# STELLA.net
KiCad netlist of a schematic drawn in EAGLE
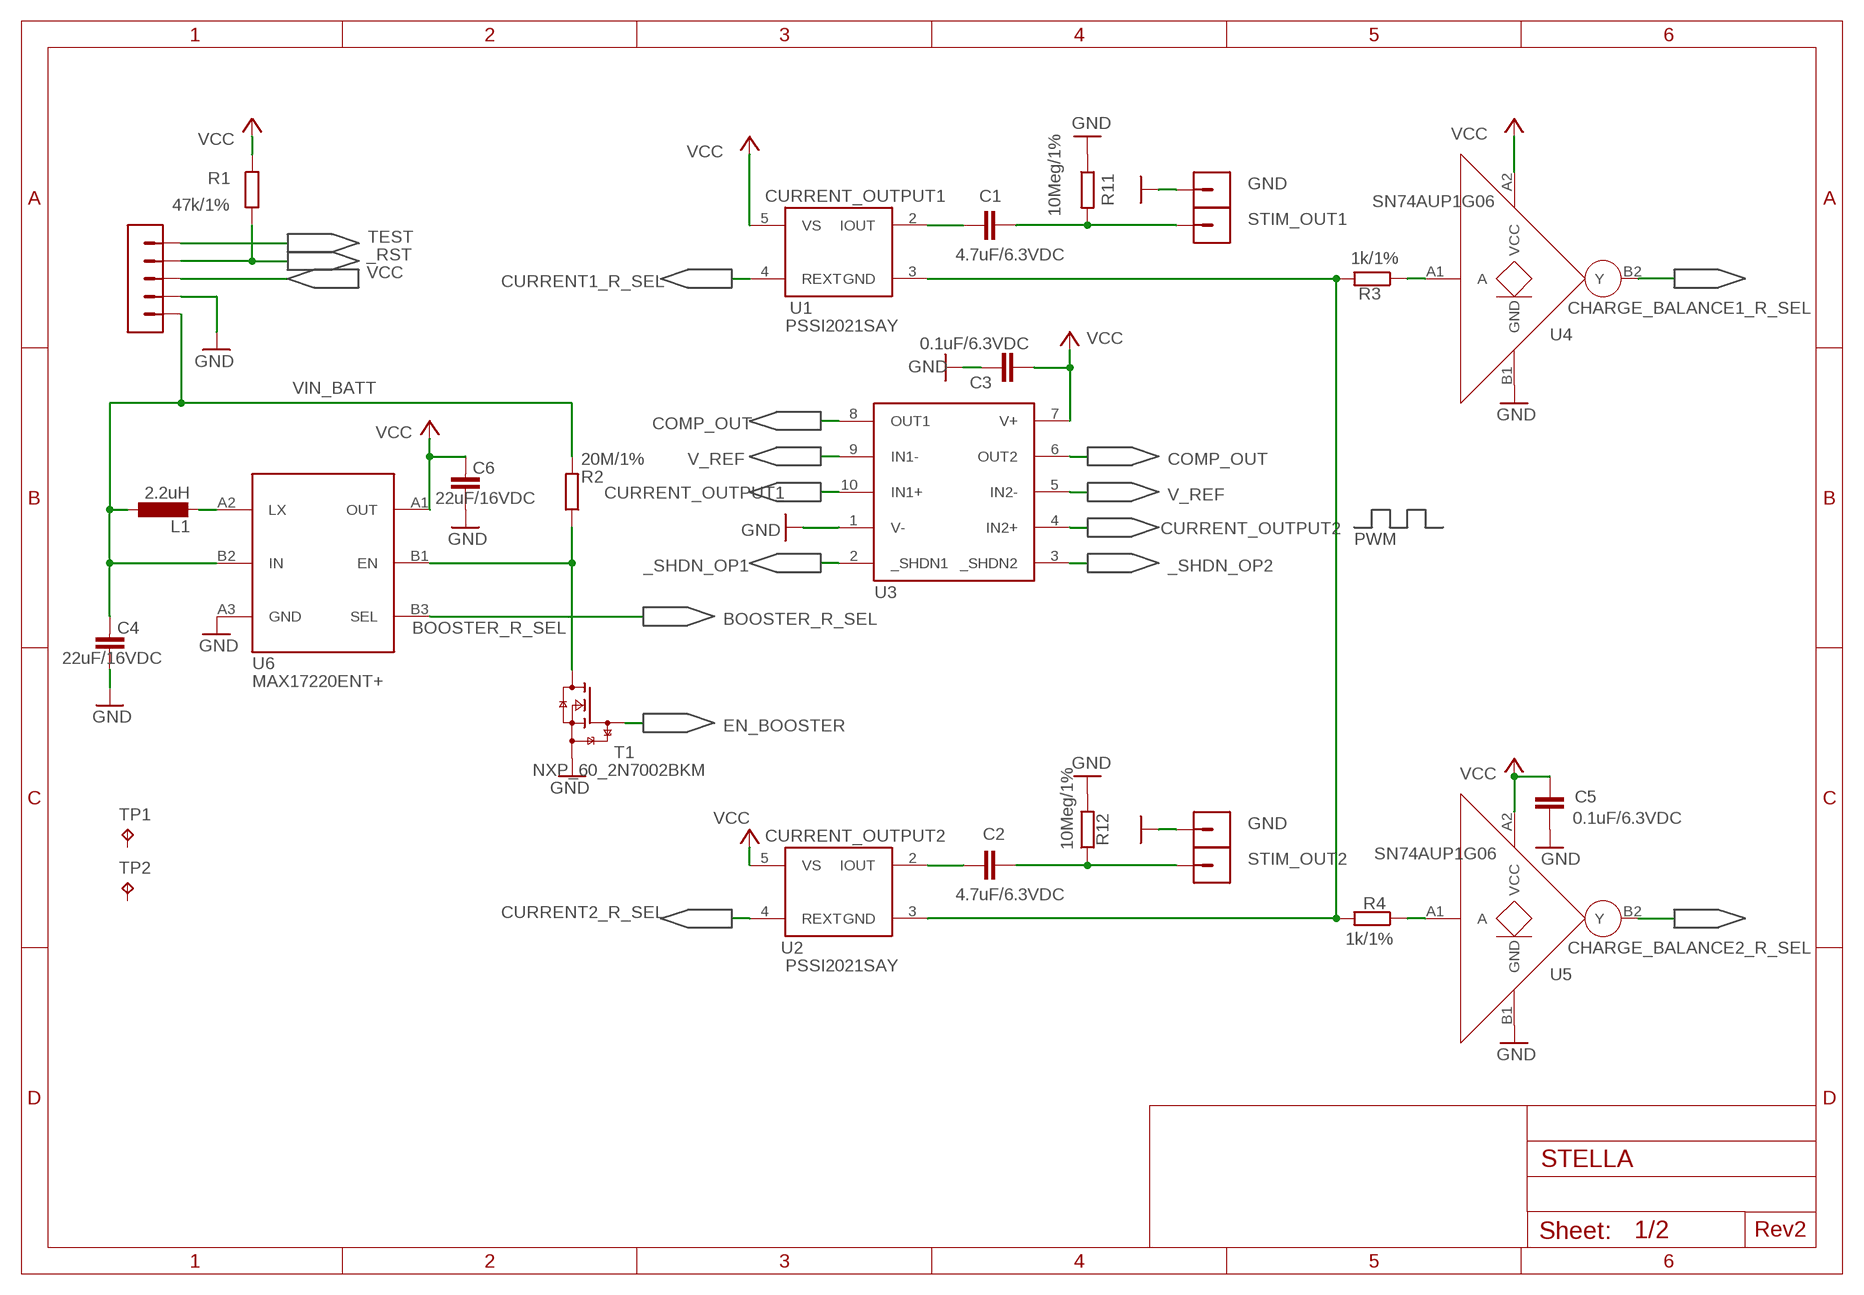
[diagram p0: schematic, sheet 1]
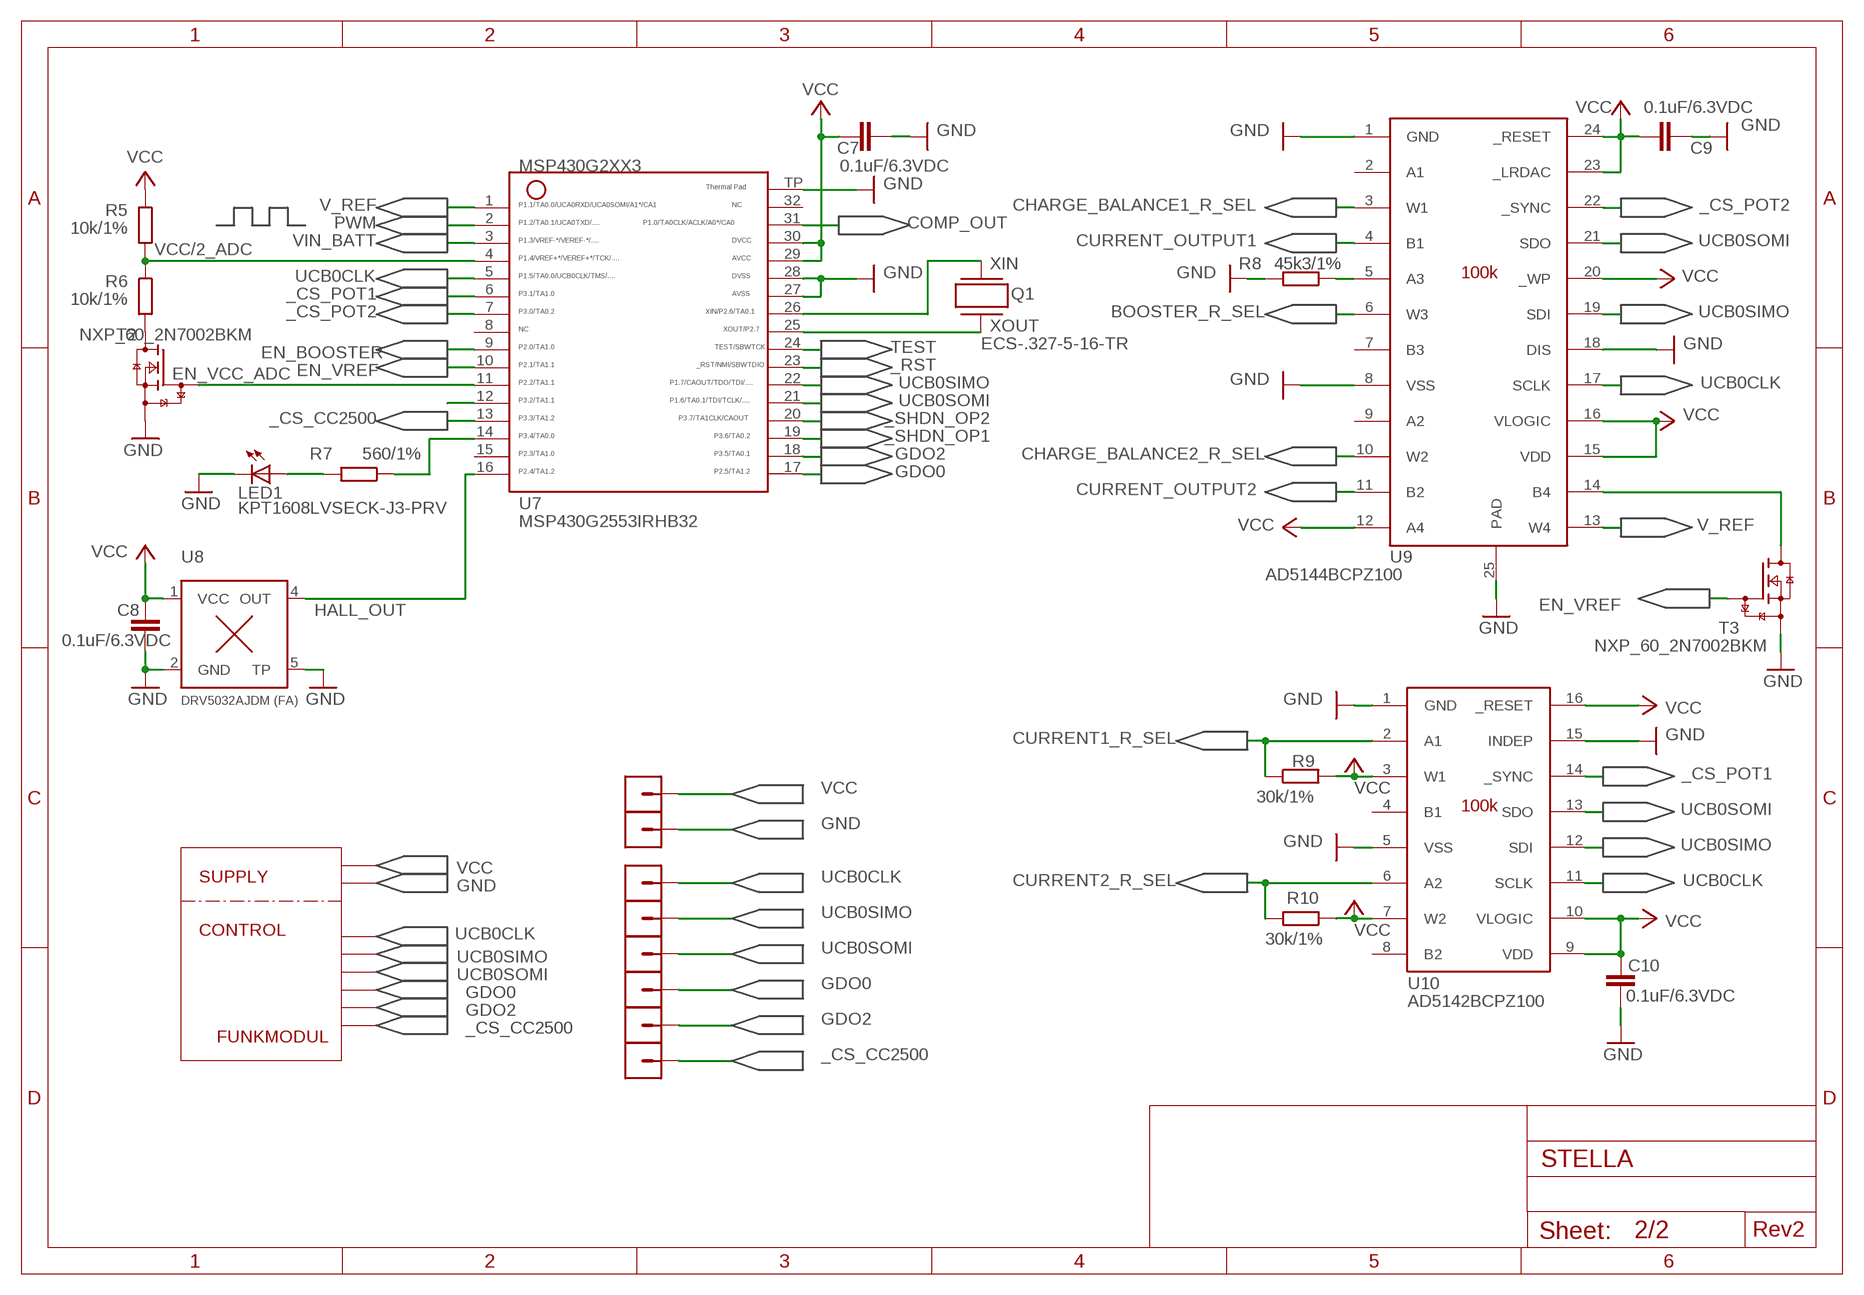
[diagram p1: schematic, sheet 2]

(export (version "E")
  (design (tool "Eeschema 10.0.6"))
  (components
    (comp (ref "C7")
      (value "0.1uF/6.3VDC")
      (footprint "eagle-import:C0402")
      (libsource (lib "eagle-import") (part "C-EUC0402"))
    )
    (comp (ref "C8")
      (value "0.1uF/6.3VDC")
      (footprint "eagle-import:C0402")
      (libsource (lib "eagle-import") (part "C-EUC0402"))
    )
    (comp (ref "C9")
      (value "0.1uF/6.3VDC")
      (footprint "eagle-import:C0402")
      (libsource (lib "eagle-import") (part "C-EUC0402"))
    )
    (comp (ref "C10")
      (value "0.1uF/6.3VDC")
      (footprint "eagle-import:C0402")
      (libsource (lib "eagle-import") (part "C-EUC0402"))
    )
    (comp (ref "LED1")
      (value "KPT1608LVSECK-J3-PRV")
      (footprint "eagle-import:LED_CHIP-LED0603")
      (libsource (lib "eagle-import") (part "LED_LEDCHIP-LED0603"))
    )
    (comp (ref "Q1")
      (value "ECS-.327-5-16-TR")
      (footprint "eagle-import:CRYSTAL_ECX_16_32768_ECX-16")
      (libsource (lib "eagle-import") (part "CRYSTAL_ECX_16_32768_ECX-16"))
    )
    (comp (ref "R5")
      (value "10k/1%")
      (footprint "eagle-import:R0402")
      (libsource (lib "eagle-import") (part "R-EU_R0402"))
    )
    (comp (ref "R6")
      (value "10k/1%")
      (footprint "eagle-import:R0402")
      (libsource (lib "eagle-import") (part "R-EU_R0402"))
    )
    (comp (ref "R7")
      (value "560/1%")
      (footprint "eagle-import:R0402")
      (libsource (lib "eagle-import") (part "R-EU_R0402"))
    )
    (comp (ref "R8")
      (value "45k3/1%")
      (footprint "eagle-import:R0402")
      (libsource (lib "eagle-import") (part "R-EU_R0402"))
    )
    (comp (ref "R9")
      (value "30k/1%")
      (footprint "eagle-import:R0402")
      (libsource (lib "eagle-import") (part "R-EU_R0402"))
    )
    (comp (ref "R10")
      (value "30k/1%")
      (footprint "eagle-import:R0402")
      (libsource (lib "eagle-import") (part "R-EU_R0402"))
    )
    (comp (ref "T2")
      (value "NXP_60_2N7002BKM")
      (footprint "eagle-import:NXP_60_SOT883(B)")
      (libsource (lib "eagle-import") (part "NXP_60_2N7002BKM"))
    )
    (comp (ref "T3")
      (value "NXP_60_2N7002BKM")
      (footprint "eagle-import:NXP_60_SOT883(B)")
      (libsource (lib "eagle-import") (part "NXP_60_2N7002BKM"))
    )
    (comp (ref "U7")
      (value "MSP430G2553IRHB32")
      (footprint "eagle-import:RHB32")
      (libsource (lib "eagle-import") (part "G2XX3---RHB32"))
    )
    (comp (ref "U8")
      (value "DRV5032AJDM (FA)")
      (footprint "eagle-import:DRV5032_DRV5032_X2SON")
      (libsource (lib "eagle-import") (part "DRV5032_DRV5032"))
    )
    (comp (ref "U9")
      (value "AD5144BCPZ100")
      (footprint "eagle-import:AD5144_AD5144_LFCSP")
      (libsource (lib "eagle-import") (part "AD5144_AD5144"))
    )
    (comp (ref "U10")
      (value "AD5142BCPZ100")
      (footprint "eagle-import:AD5122_AD5142_LFCSP")
      (libsource (lib "eagle-import") (part "AD5122_AD5142"))
    )
    (comp (ref "X6")
      (value "1PIN_INTERFACE")
      (footprint "eagle-import:1PIN_INTERFACE")
      (libsource (lib "eagle-import") (part "1PIN_INTERFACE"))
    )
    (comp (ref "X7")
      (value "1PIN_INTERFACE")
      (footprint "eagle-import:1PIN_INTERFACE")
      (libsource (lib "eagle-import") (part "1PIN_INTERFACE"))
    )
    (comp (ref "X8")
      (value "1PIN_INTERFACE")
      (footprint "eagle-import:1PIN_INTERFACE")
      (libsource (lib "eagle-import") (part "1PIN_INTERFACE"))
    )
    (comp (ref "X9")
      (value "1PIN_INTERFACE")
      (footprint "eagle-import:1PIN_INTERFACE")
      (libsource (lib "eagle-import") (part "1PIN_INTERFACE"))
    )
    (comp (ref "X10")
      (value "1PIN_INTERFACE")
      (footprint "eagle-import:1PIN_INTERFACE")
      (libsource (lib "eagle-import") (part "1PIN_INTERFACE"))
    )
    (comp (ref "X11")
      (value "1PIN_INTERFACE")
      (footprint "eagle-import:1PIN_INTERFACE")
      (libsource (lib "eagle-import") (part "1PIN_INTERFACE"))
    )
    (comp (ref "X12")
      (value "1PIN_INTERFACE")
      (footprint "eagle-import:1PIN_INTERFACE")
      (libsource (lib "eagle-import") (part "1PIN_INTERFACE"))
    )
    (comp (ref "X13")
      (value "1PIN_INTERFACE")
      (footprint "eagle-import:1PIN_INTERFACE")
      (libsource (lib "eagle-import") (part "1PIN_INTERFACE"))
    )
    (comp (ref "C1")
      (value "4.7uF/6.3VDC")
      (footprint "eagle-import:C0402")
      (libsource (lib "eagle-import") (part "C-EUC0402"))
    )
    (comp (ref "C2")
      (value "4.7uF/6.3VDC")
      (footprint "eagle-import:C0402")
      (libsource (lib "eagle-import") (part "C-EUC0402"))
    )
    (comp (ref "C3")
      (value "0.1uF/6.3VDC")
      (footprint "eagle-import:C0402")
      (libsource (lib "eagle-import") (part "C-EUC0402"))
    )
    (comp (ref "C4")
      (value "22uF/16VDC")
      (footprint "eagle-import:MYRCL_0603")
      (libsource (lib "eagle-import") (part "MYRCL_C0603"))
    )
    (comp (ref "C5")
      (value "0.1uF/6.3VDC")
      (footprint "eagle-import:C0402")
      (libsource (lib "eagle-import") (part "C-EUC0402"))
    )
    (comp (ref "C6")
      (value "22uF/16VDC")
      (footprint "eagle-import:MYRCL_0603")
      (libsource (lib "eagle-import") (part "MYRCL_C0603"))
    )
    (comp (ref "L1")
      (value "2.2uH")
      (footprint "eagle-import:L0402")
      (libsource (lib "eagle-import") (part "L-EU"))
    )
    (comp (ref "R1")
      (value "47k/1%")
      (footprint "eagle-import:R0402")
      (libsource (lib "eagle-import") (part "R-EU_R0402"))
    )
    (comp (ref "R2")
      (value "20M/1%")
      (footprint "eagle-import:R0402")
      (libsource (lib "eagle-import") (part "R-EU_R0402"))
    )
    (comp (ref "R3")
      (value "1k/1%")
      (footprint "eagle-import:R0402")
      (libsource (lib "eagle-import") (part "R-EU_R0402"))
    )
    (comp (ref "R4")
      (value "1k/1%")
      (footprint "eagle-import:R0402")
      (libsource (lib "eagle-import") (part "R-EU_R0402"))
    )
    (comp (ref "R11")
      (value "10Meg/1%")
      (footprint "eagle-import:R0402")
      (libsource (lib "eagle-import") (part "R-EU_R0402"))
    )
    (comp (ref "R12")
      (value "10Meg/1%")
      (footprint "eagle-import:R0402")
      (libsource (lib "eagle-import") (part "R-EU_R0402"))
    )
    (comp (ref "T1")
      (value "NXP_60_2N7002BKM")
      (footprint "eagle-import:NXP_60_SOT883(B)")
      (libsource (lib "eagle-import") (part "NXP_60_2N7002BKM"))
    )
    (comp (ref "TP1")
      (value "TPTP06SQ")
      (footprint "eagle-import:TP06SQ")
      (libsource (lib "eagle-import") (part "TPTP06SQ"))
    )
    (comp (ref "TP2")
      (value "TPTP06SQ")
      (footprint "eagle-import:TP06SQ")
      (libsource (lib "eagle-import") (part "TPTP06SQ"))
    )
    (comp (ref "U1")
      (value "PSSI2021SAY")
      (footprint "eagle-import:SOT353")
      (libsource (lib "eagle-import") (part "PSSI2021SAY"))
    )
    (comp (ref "U2")
      (value "PSSI2021SAY")
      (footprint "eagle-import:SOT353")
      (libsource (lib "eagle-import") (part "PSSI2021SAY"))
    )
    (comp (ref "U3")
      (value "TLV_9002S_TLV9002S_RUG")
      (footprint "eagle-import:TLV_9002S_TLV9002S_RUG")
      (libsource (lib "eagle-import") (part "TLV_9002S_TLV9002S_RUG"))
    )
    (comp (ref "U4")
      (value "SN74AUP1G06")
      (footprint "eagle-import:SN74AUP1G06_SN74AUP1G06YFPR")
      (libsource (lib "eagle-import") (part "SN74AUP1G06_SN74AUP1G06"))
    )
    (comp (ref "U5")
      (value "SN74AUP1G06")
      (footprint "eagle-import:SN74AUP1G06_SN74AUP1G06YFPR")
      (libsource (lib "eagle-import") (part "SN74AUP1G06_SN74AUP1G06"))
    )
    (comp (ref "U6")
      (value "MAX17220ENT+")
      (footprint "eagle-import:MAX17220ENT")
      (libsource (lib "eagle-import") (part "MAX17220"))
    )
    (comp (ref "X1")
      (value "1PIN_INTERFACE")
      (footprint "eagle-import:1PIN_INTERFACE")
      (libsource (lib "eagle-import") (part "1PIN_INTERFACE"))
    )
    (comp (ref "X2")
      (value "1PIN_INTERFACE")
      (footprint "eagle-import:1PIN_INTERFACE")
      (libsource (lib "eagle-import") (part "1PIN_INTERFACE"))
    )
    (comp (ref "X3")
      (value "1PIN_INTERFACE")
      (footprint "eagle-import:1PIN_INTERFACE")
      (libsource (lib "eagle-import") (part "1PIN_INTERFACE"))
    )
    (comp (ref "X4")
      (value "1PIN_INTERFACE")
      (footprint "eagle-import:1PIN_INTERFACE")
      (libsource (lib "eagle-import") (part "1PIN_INTERFACE"))
    )
    (comp (ref "X5")
      (value "5PIN")
      (footprint "eagle-import:0.9MM_0.6MM")
      (libsource (lib "eagle-import") (part "5PIN"))
    )
  )
  (nets
    (net (code "1") (name "BOOSTER_R_SEL") (class "Default")
      (node (ref "U6") (pin "B3") (pinfunction "SEL_B3") (pintype "bidirectional"))
      (node (ref "U9") (pin "6") (pinfunction "W3_6") (pintype "bidirectional"))
    )
    (net (code "2") (name "CHARGE_BALANCE1_R_SEL") (class "Default")
      (node (ref "U4") (pin "B2") (pinfunction "Y_B2") (pintype "bidirectional"))
      (node (ref "U9") (pin "3") (pinfunction "W1_3") (pintype "bidirectional"))
    )
    (net (code "3") (name "CHARGE_BALANCE2_R_SEL") (class "Default")
      (node (ref "U5") (pin "B2") (pinfunction "Y_B2") (pintype "bidirectional"))
      (node (ref "U9") (pin "10") (pinfunction "W2_10") (pintype "bidirectional"))
    )
    (net (code "4") (name "COMP_OUT") (class "Default")
      (node (ref "U3") (pin "6") (pinfunction "OUT2_6") (pintype "bidirectional"))
      (node (ref "U3") (pin "8") (pinfunction "OUT1_8") (pintype "bidirectional"))
      (node (ref "U7") (pin "31") (pinfunction "31_31") (pintype "bidirectional"))
    )
    (net (code "5") (name "CURRENT1_R_SEL") (class "Default")
      (node (ref "R9") (pin "1") (pinfunction "1_1") (pintype "passive"))
      (node (ref "U1") (pin "4") (pinfunction "REXT_4") (pintype "passive"))
      (node (ref "U10") (pin "2") (pinfunction "A1_2") (pintype "bidirectional"))
    )
    (net (code "6") (name "CURRENT2_R_SEL") (class "Default")
      (node (ref "R10") (pin "2") (pinfunction "2_2") (pintype "passive"))
      (node (ref "U10") (pin "6") (pinfunction "A2_6") (pintype "bidirectional"))
      (node (ref "U2") (pin "4") (pinfunction "REXT_4") (pintype "passive"))
    )
    (net (code "7") (name "CURRENT_OUTPUT1") (class "Default")
      (node (ref "C1") (pin "2") (pinfunction "2_2") (pintype "passive"))
      (node (ref "U1") (pin "2") (pinfunction "IOUT_2") (pintype "passive"))
      (node (ref "U3") (pin "10") (pinfunction "IN1+_10") (pintype "bidirectional"))
      (node (ref "U9") (pin "4") (pinfunction "B1_4") (pintype "bidirectional"))
    )
    (net (code "8") (name "CURRENT_OUTPUT2") (class "Default")
      (node (ref "C2") (pin "2") (pinfunction "2_2") (pintype "passive"))
      (node (ref "U2") (pin "2") (pinfunction "IOUT_2") (pintype "passive"))
      (node (ref "U3") (pin "4") (pinfunction "IN2+_4") (pintype "bidirectional"))
      (node (ref "U9") (pin "11") (pinfunction "B2_11") (pintype "bidirectional"))
    )
    (net (code "9") (name "EN_BOOSTER") (class "Default")
      (node (ref "T1") (pin "1") (pinfunction "G_1") (pintype "passive"))
      (node (ref "U7") (pin "9") (pinfunction "9_9") (pintype "bidirectional"))
    )
    (net (code "10") (name "EN_VCC_ADC") (class "Default")
      (node (ref "T2") (pin "1") (pinfunction "G_1") (pintype "passive"))
      (node (ref "U7") (pin "11") (pinfunction "11_11") (pintype "bidirectional"))
    )
    (net (code "11") (name "EN_VREF") (class "Default")
      (node (ref "T3") (pin "1") (pinfunction "G_1") (pintype "passive"))
      (node (ref "U7") (pin "10") (pinfunction "10_10") (pintype "bidirectional"))
    )
    (net (code "12") (name "GDO0") (class "Default")
      (node (ref "U7") (pin "17") (pinfunction "17_17") (pintype "bidirectional"))
      (node (ref "X11") (pin "1") (pinfunction "1_1") (pintype "bidirectional"))
    )
    (net (code "13") (name "GDO2") (class "Default")
      (node (ref "U7") (pin "18") (pinfunction "18_18") (pintype "bidirectional"))
      (node (ref "X12") (pin "1") (pinfunction "1_1") (pintype "bidirectional"))
    )
    (net (code "14") (name "GND") (class "Default")
      (node (ref "C10") (pin "2") (pinfunction "2_2") (pintype "passive"))
      (node (ref "C3") (pin "2") (pinfunction "2_2") (pintype "passive"))
      (node (ref "C4") (pin "2") (pinfunction "P$2_2") (pintype "passive"))
      (node (ref "C5") (pin "2") (pinfunction "2_2") (pintype "passive"))
      (node (ref "C6") (pin "2") (pinfunction "P$2_2") (pintype "passive"))
      (node (ref "C7") (pin "2") (pinfunction "2_2") (pintype "passive"))
      (node (ref "C8") (pin "2") (pinfunction "2_2") (pintype "passive"))
      (node (ref "C9") (pin "1") (pinfunction "1_1") (pintype "passive"))
      (node (ref "LED1") (pin "C") (pinfunction "C_C") (pintype "passive"))
      (node (ref "R11") (pin "1") (pinfunction "1_1") (pintype "passive"))
      (node (ref "R12") (pin "2") (pinfunction "2_2") (pintype "passive"))
      (node (ref "R8") (pin "2") (pinfunction "2_2") (pintype "passive"))
      (node (ref "T1") (pin "2") (pinfunction "S_2") (pintype "passive"))
      (node (ref "T2") (pin "2") (pinfunction "S_2") (pintype "passive"))
      (node (ref "T3") (pin "2") (pinfunction "S_2") (pintype "passive"))
      (node (ref "U10") (pin "1") (pinfunction "GND_1") (pintype "bidirectional"))
      (node (ref "U10") (pin "15") (pinfunction "INDEP_15") (pintype "bidirectional"))
      (node (ref "U10") (pin "5") (pinfunction "VSS_5") (pintype "bidirectional"))
      (node (ref "U3") (pin "1") (pinfunction "V-_1") (pintype "bidirectional"))
      (node (ref "U4") (pin "B1") (pinfunction "GND_B1") (pintype "bidirectional"))
      (node (ref "U5") (pin "B1") (pinfunction "GND_B1") (pintype "bidirectional"))
      (node (ref "U6") (pin "A3") (pinfunction "GND_A3") (pintype "bidirectional"))
      (node (ref "U7") (pin "27") (pinfunction "27_27") (pintype "bidirectional"))
      (node (ref "U7") (pin "28") (pinfunction "28_28") (pintype "bidirectional"))
      (node (ref "U7") (pin "TP") (pinfunction "TP_TP") (pintype "bidirectional"))
      (node (ref "U8") (pin "2") (pinfunction "GND_2") (pintype "bidirectional"))
      (node (ref "U8") (pin "5") (pinfunction "TP_5") (pintype "bidirectional"))
      (node (ref "U9") (pin "1") (pinfunction "GND_1") (pintype "bidirectional"))
      (node (ref "U9") (pin "18") (pinfunction "DIS_18") (pintype "bidirectional"))
      (node (ref "U9") (pin "25") (pinfunction "PAD_25") (pintype "bidirectional"))
      (node (ref "U9") (pin "8") (pinfunction "VSS_8") (pintype "bidirectional"))
      (node (ref "X2") (pin "1") (pinfunction "1_1") (pintype "bidirectional"))
      (node (ref "X4") (pin "1") (pinfunction "1_1") (pintype "bidirectional"))
      (node (ref "X5") (pin "2") (pinfunction "2_2") (pintype "bidirectional"))
      (node (ref "X7") (pin "1") (pinfunction "1_1") (pintype "bidirectional"))
    )
    (net (code "15") (name "HALL_OUT") (class "Default")
      (node (ref "U7") (pin "16") (pinfunction "16_16") (pintype "bidirectional"))
      (node (ref "U8") (pin "4") (pinfunction "OUT_4") (pintype "bidirectional"))
    )
    (net (code "16") (name "Net-(LED1-PadA)") (class "Default")
      (node (ref "LED1") (pin "A") (pinfunction "A_A") (pintype "passive"))
      (node (ref "R7") (pin "2") (pinfunction "2_2") (pintype "passive"))
    )
    (net (code "17") (name "Net-(R7-Pad1)") (class "Default")
      (node (ref "R7") (pin "1") (pinfunction "1_1") (pintype "passive"))
      (node (ref "U7") (pin "14") (pinfunction "14_14") (pintype "bidirectional"))
    )
    (net (code "18") (name "Net-(T1-D)") (class "Default")
      (node (ref "R2") (pin "1") (pinfunction "1_1") (pintype "passive"))
      (node (ref "T1") (pin "3") (pinfunction "D_3") (pintype "passive"))
      (node (ref "U6") (pin "B1") (pinfunction "EN_B1") (pintype "bidirectional"))
    )
    (net (code "19") (name "Net-(T2-D)") (class "Default")
      (node (ref "R6") (pin "2") (pinfunction "2_2") (pintype "passive"))
      (node (ref "T2") (pin "3") (pinfunction "D_3") (pintype "passive"))
    )
    (net (code "20") (name "Net-(T3-D)") (class "Default")
      (node (ref "T3") (pin "3") (pinfunction "D_3") (pintype "passive"))
      (node (ref "U9") (pin "14") (pinfunction "B4_14") (pintype "bidirectional"))
    )
    (net (code "21") (name "Net-(U4-A)") (class "Default")
      (node (ref "R3") (pin "1") (pinfunction "1_1") (pintype "passive"))
      (node (ref "U4") (pin "A1") (pinfunction "A_A1") (pintype "bidirectional"))
    )
    (net (code "22") (name "Net-(U5-A)") (class "Default")
      (node (ref "R4") (pin "1") (pinfunction "1_1") (pintype "passive"))
      (node (ref "U5") (pin "A1") (pinfunction "A_A1") (pintype "bidirectional"))
    )
    (net (code "23") (name "Net-(U6-LX)") (class "Default")
      (node (ref "L1") (pin "2") (pinfunction "2_2") (pintype "passive"))
      (node (ref "U6") (pin "A2") (pinfunction "LX_A2") (pintype "bidirectional"))
    )
    (net (code "24") (name "Net-(U9-A3)") (class "Default")
      (node (ref "R8") (pin "1") (pinfunction "1_1") (pintype "passive"))
      (node (ref "U9") (pin "5") (pinfunction "A3_5") (pintype "bidirectional"))
    )
    (net (code "25") (name "PWM") (class "Default")
      (node (ref "R3") (pin "2") (pinfunction "2_2") (pintype "passive"))
      (node (ref "R4") (pin "2") (pinfunction "2_2") (pintype "passive"))
      (node (ref "U1") (pin "3") (pinfunction "GND_3") (pintype "power_in"))
      (node (ref "U2") (pin "3") (pinfunction "GND_3") (pintype "power_in"))
      (node (ref "U7") (pin "2") (pinfunction "2_2") (pintype "bidirectional"))
    )
    (net (code "26") (name "STIM_OUT1") (class "Default")
      (node (ref "C1") (pin "1") (pinfunction "1_1") (pintype "passive"))
      (node (ref "R11") (pin "2") (pinfunction "2_2") (pintype "passive"))
      (node (ref "X1") (pin "1") (pinfunction "1_1") (pintype "bidirectional"))
    )
    (net (code "27") (name "STIM_OUT2") (class "Default")
      (node (ref "C2") (pin "1") (pinfunction "1_1") (pintype "passive"))
      (node (ref "R12") (pin "1") (pinfunction "1_1") (pintype "passive"))
      (node (ref "X3") (pin "1") (pinfunction "1_1") (pintype "bidirectional"))
    )
    (net (code "28") (name "TEST") (class "Default")
      (node (ref "U7") (pin "24") (pinfunction "24_24") (pintype "bidirectional"))
      (node (ref "X5") (pin "5") (pinfunction "5_5") (pintype "bidirectional"))
    )
    (net (code "29") (name "UCB0CLK") (class "Default")
      (node (ref "U10") (pin "11") (pinfunction "SCLK_11") (pintype "bidirectional"))
      (node (ref "U7") (pin "5") (pinfunction "5_5") (pintype "bidirectional"))
      (node (ref "U9") (pin "17") (pinfunction "SCLK_17") (pintype "bidirectional"))
      (node (ref "X8") (pin "1") (pinfunction "1_1") (pintype "bidirectional"))
    )
    (net (code "30") (name "UCB0SIMO") (class "Default")
      (node (ref "U10") (pin "12") (pinfunction "SDI_12") (pintype "bidirectional"))
      (node (ref "U7") (pin "22") (pinfunction "22_22") (pintype "bidirectional"))
      (node (ref "U9") (pin "19") (pinfunction "SDI_19") (pintype "bidirectional"))
      (node (ref "X9") (pin "1") (pinfunction "1_1") (pintype "bidirectional"))
    )
    (net (code "31") (name "UCB0SOMI") (class "Default")
      (node (ref "U10") (pin "13") (pinfunction "SDO_13") (pintype "bidirectional"))
      (node (ref "U7") (pin "21") (pinfunction "21_21") (pintype "bidirectional"))
      (node (ref "U9") (pin "21") (pinfunction "SDO_21") (pintype "bidirectional"))
      (node (ref "X10") (pin "1") (pinfunction "1_1") (pintype "bidirectional"))
    )
    (net (code "32") (name "VCC") (class "Default")
      (node (ref "C10") (pin "1") (pinfunction "1_1") (pintype "passive"))
      (node (ref "C3") (pin "1") (pinfunction "1_1") (pintype "passive"))
      (node (ref "C5") (pin "1") (pinfunction "1_1") (pintype "passive"))
      (node (ref "C6") (pin "1") (pinfunction "P$1_1") (pintype "passive"))
      (node (ref "C7") (pin "1") (pinfunction "1_1") (pintype "passive"))
      (node (ref "C8") (pin "1") (pinfunction "1_1") (pintype "passive"))
      (node (ref "C9") (pin "2") (pinfunction "2_2") (pintype "passive"))
      (node (ref "R1") (pin "1") (pinfunction "1_1") (pintype "passive"))
      (node (ref "R10") (pin "1") (pinfunction "1_1") (pintype "passive"))
      (node (ref "R5") (pin "1") (pinfunction "1_1") (pintype "passive"))
      (node (ref "R9") (pin "2") (pinfunction "2_2") (pintype "passive"))
      (node (ref "U1") (pin "5") (pinfunction "VS_5") (pintype "power_in"))
      (node (ref "U10") (pin "10") (pinfunction "VLOGIC_10") (pintype "bidirectional"))
      (node (ref "U10") (pin "16") (pinfunction "_RESET_16") (pintype "bidirectional"))
      (node (ref "U10") (pin "3") (pinfunction "W1_3") (pintype "bidirectional"))
      (node (ref "U10") (pin "7") (pinfunction "W2_7") (pintype "bidirectional"))
      (node (ref "U10") (pin "9") (pinfunction "VDD_9") (pintype "bidirectional"))
      (node (ref "U2") (pin "5") (pinfunction "VS_5") (pintype "power_in"))
      (node (ref "U3") (pin "7") (pinfunction "V+_7") (pintype "bidirectional"))
      (node (ref "U4") (pin "A2") (pinfunction "VCC_A2") (pintype "bidirectional"))
      (node (ref "U5") (pin "A2") (pinfunction "VCC_A2") (pintype "bidirectional"))
      (node (ref "U6") (pin "A1") (pinfunction "OUT_A1") (pintype "bidirectional"))
      (node (ref "U7") (pin "29") (pinfunction "29_29") (pintype "bidirectional"))
      (node (ref "U7") (pin "30") (pinfunction "30_30") (pintype "bidirectional"))
      (node (ref "U8") (pin "1") (pinfunction "VCC_1") (pintype "bidirectional"))
      (node (ref "U9") (pin "12") (pinfunction "A4_12") (pintype "bidirectional"))
      (node (ref "U9") (pin "15") (pinfunction "VDD_15") (pintype "bidirectional"))
      (node (ref "U9") (pin "16") (pinfunction "VLOGIC_16") (pintype "bidirectional"))
      (node (ref "U9") (pin "20") (pinfunction "_WP_20") (pintype "bidirectional"))
      (node (ref "U9") (pin "23") (pinfunction "_LRDAC_23") (pintype "bidirectional"))
      (node (ref "U9") (pin "24") (pinfunction "_RESET_24") (pintype "bidirectional"))
      (node (ref "X5") (pin "3") (pinfunction "3_3") (pintype "bidirectional"))
      (node (ref "X6") (pin "1") (pinfunction "1_1") (pintype "bidirectional"))
    )
    (net (code "33") (name "VCC{slash}2_ADC") (class "Default")
      (node (ref "R5") (pin "2") (pinfunction "2_2") (pintype "passive"))
      (node (ref "R6") (pin "1") (pinfunction "1_1") (pintype "passive"))
      (node (ref "U7") (pin "4") (pinfunction "4_4") (pintype "bidirectional"))
    )
    (net (code "34") (name "VIN_BATT") (class "Default")
      (node (ref "C4") (pin "1") (pinfunction "P$1_1") (pintype "passive"))
      (node (ref "L1") (pin "1") (pinfunction "1_1") (pintype "passive"))
      (node (ref "R2") (pin "2") (pinfunction "2_2") (pintype "passive"))
      (node (ref "U6") (pin "B2") (pinfunction "IN_B2") (pintype "bidirectional"))
      (node (ref "U7") (pin "3") (pinfunction "3_3") (pintype "bidirectional"))
      (node (ref "X5") (pin "1") (pinfunction "1_1") (pintype "bidirectional"))
    )
    (net (code "35") (name "V_REF") (class "Default")
      (node (ref "U3") (pin "5") (pinfunction "IN2-_5") (pintype "bidirectional"))
      (node (ref "U3") (pin "9") (pinfunction "IN1-_9") (pintype "bidirectional"))
      (node (ref "U7") (pin "1") (pinfunction "1_1") (pintype "bidirectional"))
      (node (ref "U9") (pin "13") (pinfunction "W4_13") (pintype "bidirectional"))
    )
    (net (code "36") (name "XIN") (class "Default")
      (node (ref "Q1") (pin "1") (pinfunction "1_1") (pintype "bidirectional"))
      (node (ref "U7") (pin "26") (pinfunction "26_26") (pintype "bidirectional"))
    )
    (net (code "37") (name "XOUT") (class "Default")
      (node (ref "Q1") (pin "2") (pinfunction "2_2") (pintype "bidirectional"))
      (node (ref "U7") (pin "25") (pinfunction "25_25") (pintype "bidirectional"))
    )
    (net (code "38") (name "_CS_CC2500") (class "Default")
      (node (ref "U7") (pin "13") (pinfunction "13_13") (pintype "bidirectional"))
      (node (ref "X13") (pin "1") (pinfunction "1_1") (pintype "bidirectional"))
    )
    (net (code "39") (name "_CS_POT1") (class "Default")
      (node (ref "U10") (pin "14") (pinfunction "_SYNC_14") (pintype "bidirectional"))
      (node (ref "U7") (pin "6") (pinfunction "6_6") (pintype "bidirectional"))
    )
    (net (code "40") (name "_CS_POT2") (class "Default")
      (node (ref "U7") (pin "7") (pinfunction "7_7") (pintype "bidirectional"))
      (node (ref "U9") (pin "22") (pinfunction "_SYNC_22") (pintype "bidirectional"))
    )
    (net (code "41") (name "_RST") (class "Default")
      (node (ref "R1") (pin "2") (pinfunction "2_2") (pintype "passive"))
      (node (ref "U7") (pin "23") (pinfunction "23_23") (pintype "bidirectional"))
      (node (ref "X5") (pin "4") (pinfunction "4_4") (pintype "bidirectional"))
    )
    (net (code "42") (name "_SHDN_OP1") (class "Default")
      (node (ref "U3") (pin "2") (pinfunction "_SHDN1_2") (pintype "bidirectional"))
      (node (ref "U7") (pin "19") (pinfunction "19_19") (pintype "bidirectional"))
    )
    (net (code "43") (name "_SHDN_OP2") (class "Default")
      (node (ref "U3") (pin "3") (pinfunction "_SHDN2_3") (pintype "bidirectional"))
      (node (ref "U7") (pin "20") (pinfunction "20_20") (pintype "bidirectional"))
    )
    (net (code "44") (name "unconnected-(TP1-PadTP)") (class "Default")
      (node (ref "TP1") (pin "TP") (pinfunction "TP_TP") (pintype "input"))
    )
    (net (code "45") (name "unconnected-(TP2-PadTP)") (class "Default")
      (node (ref "TP2") (pin "TP") (pinfunction "TP_TP") (pintype "input"))
    )
    (net (code "46") (name "unconnected-(U7-Pad8)") (class "Default")
      (node (ref "U7") (pin "8") (pinfunction "8_8") (pintype "bidirectional"))
    )
    (net (code "47") (name "unconnected-(U7-Pad12)") (class "Default")
      (node (ref "U7") (pin "12") (pinfunction "12_12") (pintype "bidirectional"))
    )
    (net (code "48") (name "unconnected-(U7-Pad15)") (class "Default")
      (node (ref "U7") (pin "15") (pinfunction "15_15") (pintype "bidirectional"))
    )
    (net (code "49") (name "unconnected-(U7-Pad32)") (class "Default")
      (node (ref "U7") (pin "32") (pinfunction "32_32") (pintype "bidirectional"))
    )
    (net (code "50") (name "unconnected-(U9-A1-Pad2)") (class "Default")
      (node (ref "U9") (pin "2") (pinfunction "A1_2") (pintype "bidirectional"))
    )
    (net (code "51") (name "unconnected-(U9-A2-Pad9)") (class "Default")
      (node (ref "U9") (pin "9") (pinfunction "A2_9") (pintype "bidirectional"))
    )
    (net (code "52") (name "unconnected-(U9-B3-Pad7)") (class "Default")
      (node (ref "U9") (pin "7") (pinfunction "B3_7") (pintype "bidirectional"))
    )
    (net (code "53") (name "unconnected-(U10-B1-Pad4)") (class "Default")
      (node (ref "U10") (pin "4") (pinfunction "B1_4") (pintype "bidirectional"))
    )
    (net (code "54") (name "unconnected-(U10-B2-Pad8)") (class "Default")
      (node (ref "U10") (pin "8") (pinfunction "B2_8") (pintype "bidirectional"))
    )
  )
)
